# schmitt_trigger.net
KiCad netlist of a schematic drawn in EAGLE
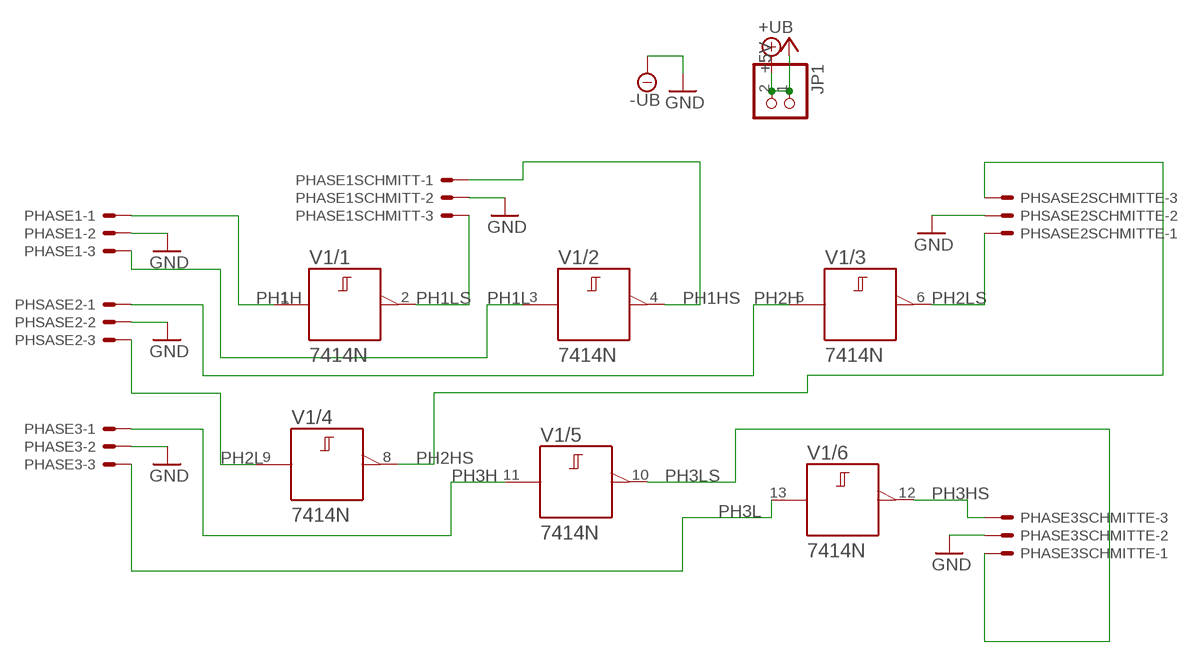
[diagram p0: schematic, sheet 1]

(export (version "E")
  (design (tool "Eeschema 10.0.6"))
  (components
    (comp (ref "JP1")
      (value "PINHD-1X2")
      (footprint "eagle-import:1X02")
      (libsource (lib "eagle-import") (part "PINHD-1X2"))
    )
    (comp (ref "PHASE1")
      (value "22-23-2031")
      (footprint "eagle-import:22-23-2031")
      (fields (field (name "MF") "MOLEX"))
      (libsource (lib "eagle-import") (part "22-23-2031"))
    )
    (comp (ref "PHASE1SCHMITT")
      (value "22-23-2031")
      (footprint "eagle-import:22-23-2031")
      (fields (field (name "MF") "MOLEX"))
      (libsource (lib "eagle-import") (part "22-23-2031"))
    )
    (comp (ref "PHASE3")
      (value "22-23-2031")
      (footprint "eagle-import:22-23-2031")
      (fields (field (name "MF") "MOLEX"))
      (libsource (lib "eagle-import") (part "22-23-2031"))
    )
    (comp (ref "PHASE3SCHMITTE")
      (value "22-23-2031")
      (footprint "eagle-import:22-23-2031")
      (fields (field (name "MF") "MOLEX"))
      (libsource (lib "eagle-import") (part "22-23-2031"))
    )
    (comp (ref "PHSASE2")
      (value "22-23-2031")
      (footprint "eagle-import:22-23-2031")
      (fields (field (name "MF") "MOLEX"))
      (libsource (lib "eagle-import") (part "22-23-2031"))
    )
    (comp (ref "PHSASE2SCHMITTE")
      (value "22-23-2031")
      (footprint "eagle-import:22-23-2031")
      (fields (field (name "MF") "MOLEX"))
      (libsource (lib "eagle-import") (part "22-23-2031"))
    )
    (comp (ref "V1")
      (value "7414N")
      (footprint "eagle-import:DIL14")
      (libsource (lib "eagle-import") (part "7414N"))
    )
  )
  (nets
    (net (code "1") (name "+5V") (class "Default")
      (node (ref "JP1") (pin "1") (pinfunction "1_1") (pintype "passive"))
      (node (ref "JP1") (pin "2") (pinfunction "2_2") (pintype "passive"))
    )
    (net (code "2") (name "-UB") (class "Default")
      (node (ref "PHASE1") (pin "2") (pinfunction "S_2") (pintype "passive"))
      (node (ref "PHASE1SCHMITT") (pin "2") (pinfunction "S_2") (pintype "passive"))
      (node (ref "PHASE3") (pin "2") (pinfunction "S_2") (pintype "passive"))
      (node (ref "PHASE3SCHMITTE") (pin "2") (pinfunction "S_2") (pintype "passive"))
      (node (ref "PHSASE2") (pin "2") (pinfunction "S_2") (pintype "passive"))
      (node (ref "PHSASE2SCHMITTE") (pin "2") (pinfunction "S_2") (pintype "passive"))
    )
    (net (code "3") (name "/PH1H") (class "Default")
      (node (ref "PHASE1") (pin "1") (pinfunction "S_1") (pintype "passive"))
      (node (ref "V1") (pin "1") (pinfunction "A_1") (pintype "input"))
    )
    (net (code "4") (name "/PH1HS") (class "Default")
      (node (ref "PHASE1SCHMITT") (pin "1") (pinfunction "S_1") (pintype "passive"))
      (node (ref "V1") (pin "4") (pinfunction "Y_4") (pintype "output"))
    )
    (net (code "5") (name "/PH1L") (class "Default")
      (node (ref "PHASE1") (pin "3") (pinfunction "S_3") (pintype "passive"))
      (node (ref "V1") (pin "3") (pinfunction "A_3") (pintype "input"))
    )
    (net (code "6") (name "/PH1LS") (class "Default")
      (node (ref "PHASE1SCHMITT") (pin "3") (pinfunction "S_3") (pintype "passive"))
      (node (ref "V1") (pin "2") (pinfunction "Y_2") (pintype "output"))
    )
    (net (code "7") (name "/PH2H") (class "Default")
      (node (ref "PHSASE2") (pin "1") (pinfunction "S_1") (pintype "passive"))
      (node (ref "V1") (pin "5") (pinfunction "A_5") (pintype "input"))
    )
    (net (code "8") (name "/PH2HS") (class "Default")
      (node (ref "PHSASE2SCHMITTE") (pin "3") (pinfunction "S_3") (pintype "passive"))
      (node (ref "V1") (pin "8") (pinfunction "Y_8") (pintype "output"))
    )
    (net (code "9") (name "/PH2L") (class "Default")
      (node (ref "PHSASE2") (pin "3") (pinfunction "S_3") (pintype "passive"))
      (node (ref "V1") (pin "9") (pinfunction "A_9") (pintype "input"))
    )
    (net (code "10") (name "/PH2LS") (class "Default")
      (node (ref "PHSASE2SCHMITTE") (pin "1") (pinfunction "S_1") (pintype "passive"))
      (node (ref "V1") (pin "6") (pinfunction "Y_6") (pintype "output"))
    )
    (net (code "11") (name "/PH3H") (class "Default")
      (node (ref "PHASE3") (pin "1") (pinfunction "S_1") (pintype "passive"))
      (node (ref "V1") (pin "11") (pinfunction "A_11") (pintype "input"))
    )
    (net (code "12") (name "/PH3HS") (class "Default")
      (node (ref "PHASE3SCHMITTE") (pin "3") (pinfunction "S_3") (pintype "passive"))
      (node (ref "V1") (pin "12") (pinfunction "Y_12") (pintype "output"))
    )
    (net (code "13") (name "/PH3L") (class "Default")
      (node (ref "PHASE3") (pin "3") (pinfunction "S_3") (pintype "passive"))
      (node (ref "V1") (pin "13") (pinfunction "A_13") (pintype "input"))
    )
    (net (code "14") (name "/PH3LS") (class "Default")
      (node (ref "PHASE3SCHMITTE") (pin "1") (pinfunction "S_1") (pintype "passive"))
      (node (ref "V1") (pin "10") (pinfunction "Y_10") (pintype "output"))
    )
  )
)
